# SCH005.net
KiCad netlist of a schematic drawn in Altium Designer
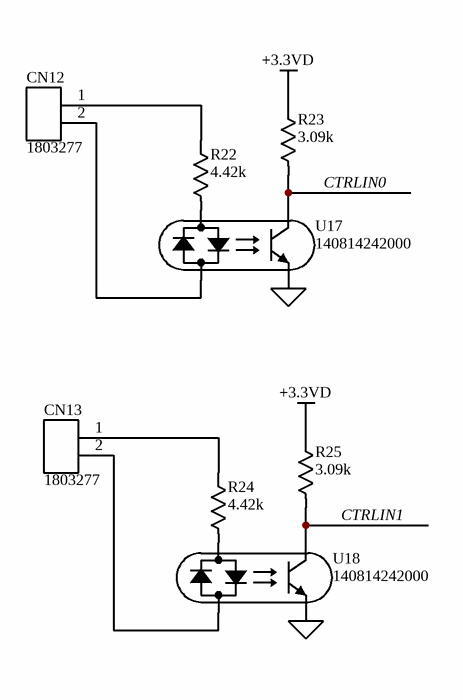
[diagram p0: SCH005.SchDoc]

(export (version "E")
  (design (tool "Eeschema 10.0.6"))
  (components
    (comp (ref "CN12")
      (value "1803277")
      (footprint "PHOENIX_1803277")
      (description "MC 1,5/2G-3,81 Pluggable Terminal Block 2 Pos 3.81mm pitch Through Hole Header")
      (fields (field (name "MANUFACTURER") "Phoenix Contact"))
      (libsource (lib "EM411-202401-RMC001-000-20240213-T10") (part "1803277"))
    )
    (comp (ref "CN13")
      (value "1803277")
      (footprint "PHOENIX_1803277")
      (description "MC 1,5/2G-3,81 Pluggable Terminal Block 2 Pos 3.81mm pitch Through Hole Header")
      (fields (field (name "MANUFACTURER") "Phoenix Contact"))
      (libsource (lib "EM411-202401-RMC001-000-20240213-T10") (part "1803277"))
    )
    (comp (ref "R22")
      (value "4.42k")
      (footprint "RESC2012X06N")
      (description "4.42k, 1%, 0.125W Thick Film Chip Resistor")
      (fields (field (name "MANUFACTURER") "Bourns") (field (name "PARTNUMBER") "CR0805-FX-4421ELF"))
      (libsource (lib "EM411-202401-RMC001-001") (part "CR0805-FX-4421ELF"))
    )
    (comp (ref "R23")
      (value "3.09k")
      (footprint "RESC2012X06N")
      (description "3.09k, 1%, 0.125W Thick Film Chip Resistor")
      (fields (field (name "MANUFACTURER") "Bourns") (field (name "PARTNUMBER") "CR0805-FX-3091ELF"))
      (libsource (lib "EM411-202401-RMC001-001") (part "CR0805-FX-3091ELF"))
    )
    (comp (ref "R24")
      (value "4.42k")
      (footprint "RESC2012X06N")
      (description "4.42k, 1%, 0.125W Thick Film Chip Resistor")
      (fields (field (name "MANUFACTURER") "Bourns") (field (name "PARTNUMBER") "CR0805-FX-4421ELF"))
      (libsource (lib "EM411-202401-RMC001-001") (part "CR0805-FX-4421ELF"))
    )
    (comp (ref "R25")
      (value "3.09k")
      (footprint "RESC2012X06N")
      (description "3.09k, 1%, 0.125W Thick Film Chip Resistor")
      (fields (field (name "MANUFACTURER") "Bourns") (field (name "PARTNUMBER") "CR0805-FX-3091ELF"))
      (libsource (lib "EM411-202401-RMC001-001") (part "CR0805-FX-3091ELF"))
    )
    (comp (ref "U17")
      (value "140814242000")
      (footprint "WURTH_140814242000")
      (description "WL-OCPT Optocoupler Phototransistor")
      (fields (field (name "MANUFACTURER") "Wurth Elektronik"))
      (libsource (lib "EM411-202401-RMC001-001") (part "140814242000"))
    )
    (comp (ref "U18")
      (value "140814242000")
      (footprint "WURTH_140814242000")
      (description "WL-OCPT Optocoupler Phototransistor")
      (fields (field (name "MANUFACTURER") "Wurth Elektronik"))
      (libsource (lib "EM411-202401-RMC001-001") (part "140814242000"))
    )
  )
  (nets
    (net (code "1") (name "+3.3VD") (class "Default")
      (node (ref "R23") (pin "2") (pinfunction "2_2") (pintype "passive"))
      (node (ref "R25") (pin "2") (pinfunction "2_2") (pintype "passive"))
    )
    (net (code "2") (name "/CTRLIN0") (class "Default")
      (node (ref "R23") (pin "1") (pinfunction "1_1") (pintype "passive"))
      (node (ref "U17") (pin "4") (pinfunction "C_4") (pintype "passive"))
    )
    (net (code "3") (name "/CTRLIN1") (class "Default")
      (node (ref "R25") (pin "1") (pinfunction "1_1") (pintype "passive"))
      (node (ref "U18") (pin "4") (pinfunction "C_4") (pintype "passive"))
    )
    (net (code "4") (name "GND") (class "Default")
      (node (ref "U17") (pin "3") (pinfunction "E_3") (pintype "passive"))
      (node (ref "U18") (pin "3") (pinfunction "E_3") (pintype "passive"))
    )
    (net (code "5") (name "Net-(CN12-Pad1)") (class "Default")
      (node (ref "CN12") (pin "1") (pinfunction "1_1") (pintype "passive"))
      (node (ref "R22") (pin "2") (pinfunction "2_2") (pintype "passive"))
    )
    (net (code "6") (name "Net-(CN13-Pad1)") (class "Default")
      (node (ref "CN13") (pin "1") (pinfunction "1_1") (pintype "passive"))
      (node (ref "R24") (pin "2") (pinfunction "2_2") (pintype "passive"))
    )
    (net (code "7") (name "Net-(U17-A)") (class "Default")
      (node (ref "R22") (pin "1") (pinfunction "1_1") (pintype "passive"))
      (node (ref "U17") (pin "1") (pinfunction "A_1") (pintype "passive"))
    )
    (net (code "8") (name "Net-(U17-K)") (class "Default")
      (node (ref "CN12") (pin "2") (pinfunction "2_2") (pintype "passive"))
      (node (ref "U17") (pin "2") (pinfunction "K_2") (pintype "passive"))
    )
    (net (code "9") (name "Net-(U18-A)") (class "Default")
      (node (ref "R24") (pin "1") (pinfunction "1_1") (pintype "passive"))
      (node (ref "U18") (pin "1") (pinfunction "A_1") (pintype "passive"))
    )
    (net (code "10") (name "Net-(U18-K)") (class "Default")
      (node (ref "CN13") (pin "2") (pinfunction "2_2") (pintype "passive"))
      (node (ref "U18") (pin "2") (pinfunction "K_2") (pintype "passive"))
    )
  )
)
